# LED_Ring_Dimmer.net
KiCad netlist of a schematic drawn in EAGLE
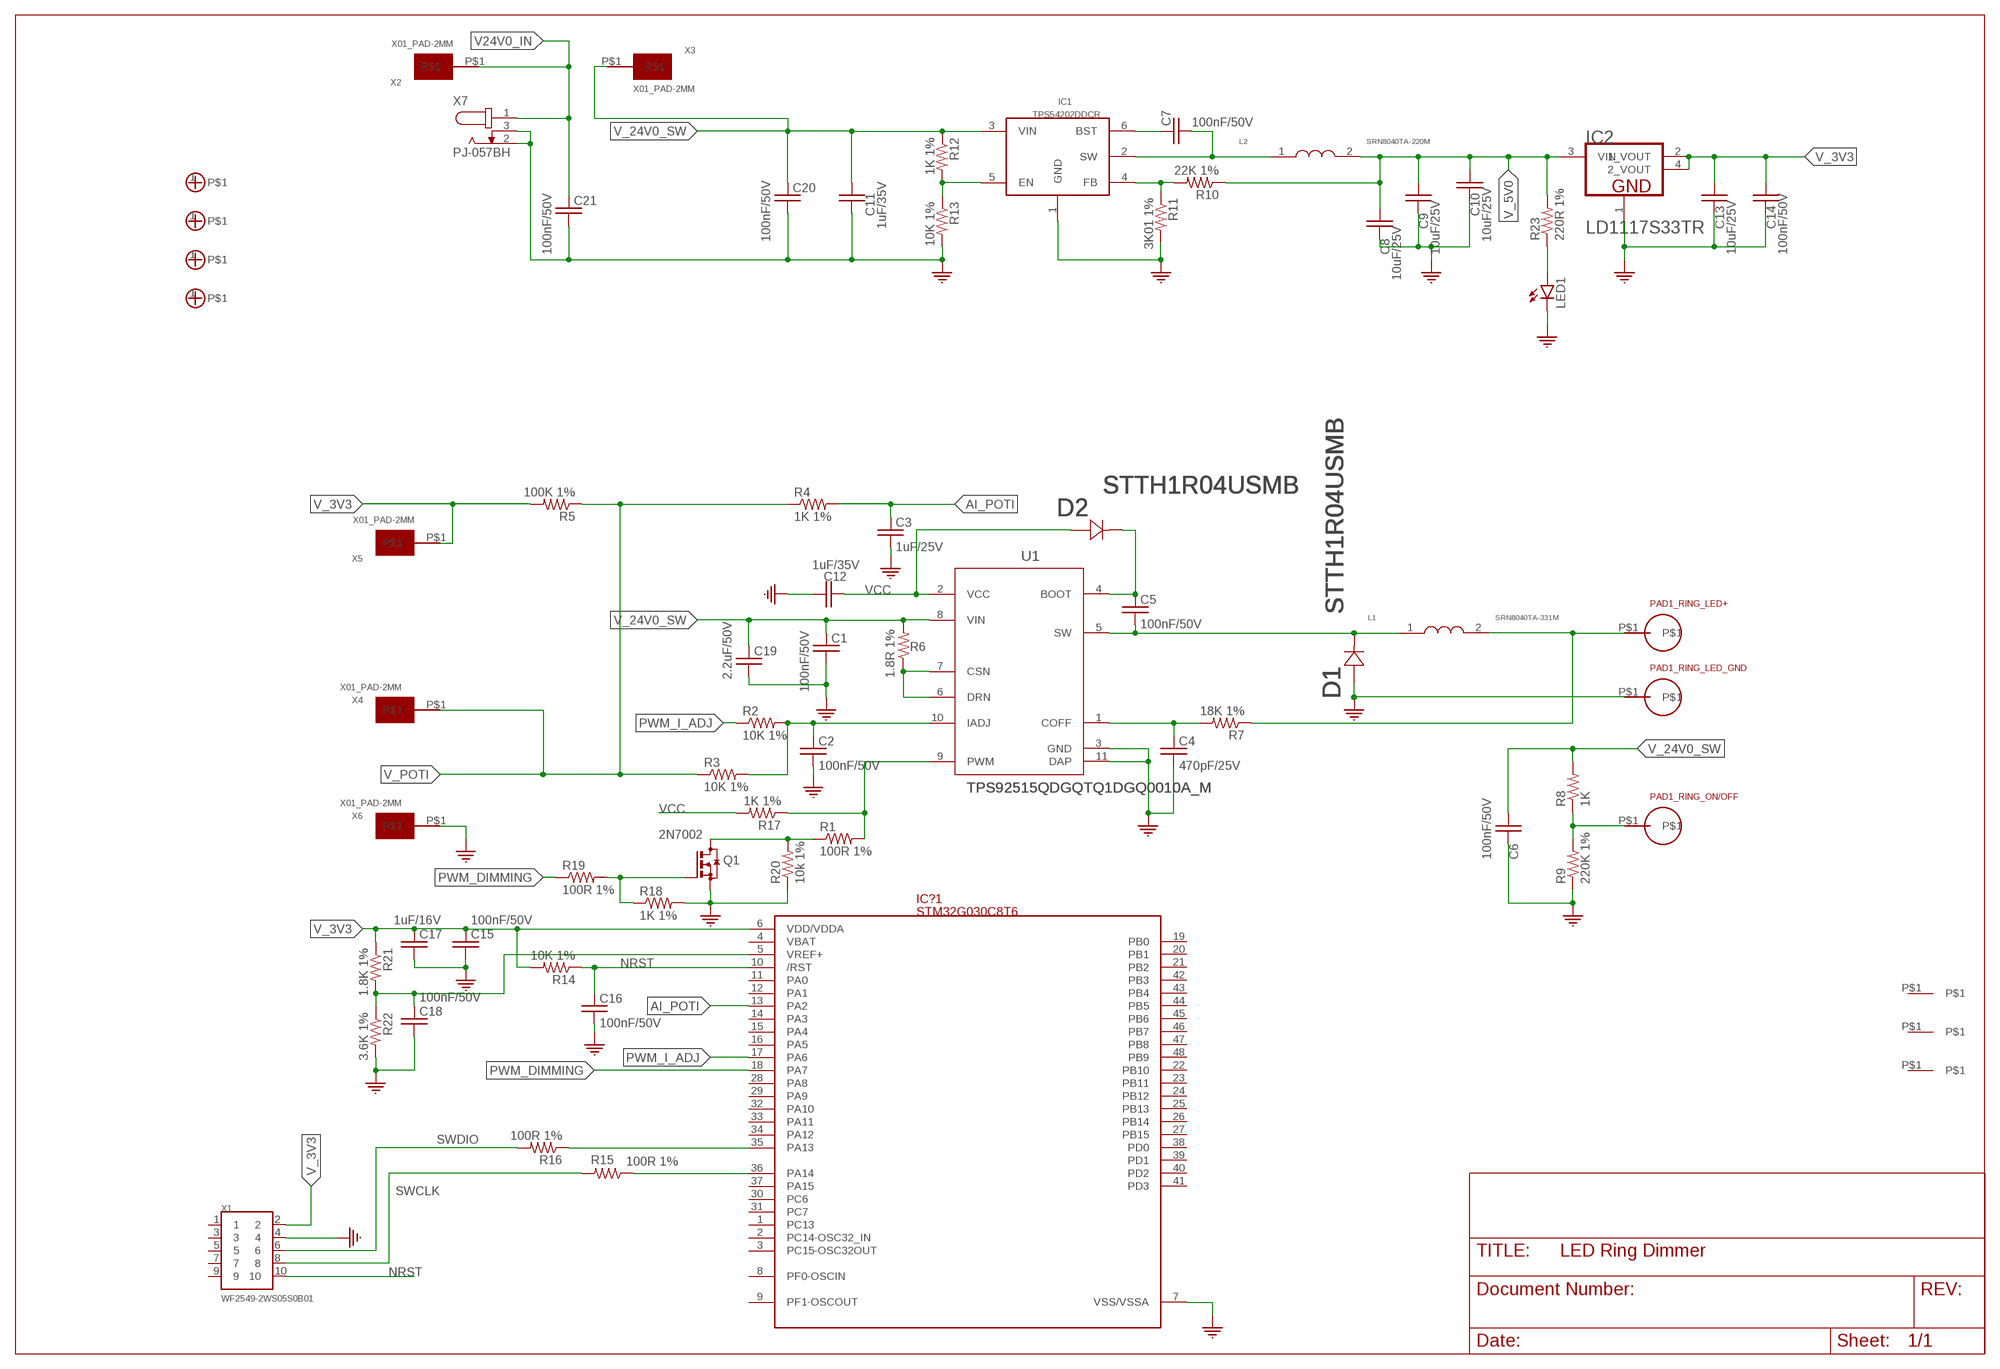
[diagram p0: schematic, sheet 1]

(export (version "E")
  (design (tool "Eeschema 10.0.6"))
  (components
    (comp (ref "C1")
      (value "100nF/50V")
      (footprint "eagle-import:EIA0603")
      (libsource (lib "eagle-import") (part "C_0603EIA0603"))
    )
    (comp (ref "C2")
      (value "100nF/50V")
      (footprint "eagle-import:EIA0603")
      (libsource (lib "eagle-import") (part "C_0603EIA0603"))
    )
    (comp (ref "C3")
      (value "1uF/25V")
      (footprint "eagle-import:EIA0603")
      (libsource (lib "eagle-import") (part "C_0603EIA0603"))
    )
    (comp (ref "C4")
      (value "470pF/25V")
      (footprint "eagle-import:EIA0603")
      (libsource (lib "eagle-import") (part "C_0603EIA0603"))
    )
    (comp (ref "C5")
      (value "100nF/50V")
      (footprint "eagle-import:EIA0603")
      (libsource (lib "eagle-import") (part "C_0603EIA0603"))
    )
    (comp (ref "C6")
      (value "100nF/50V")
      (footprint "eagle-import:EIA0603")
      (libsource (lib "eagle-import") (part "C_0603EIA0603"))
    )
    (comp (ref "C7")
      (value "100nF/50V")
      (footprint "eagle-import:EIA0603")
      (libsource (lib "eagle-import") (part "C_0603EIA0603"))
    )
    (comp (ref "C8")
      (value "10uF/25V")
      (footprint "eagle-import:EIA0603")
      (libsource (lib "eagle-import") (part "C_0603EIA0603"))
    )
    (comp (ref "C9")
      (value "10uF/25V")
      (footprint "eagle-import:EIA0603")
      (libsource (lib "eagle-import") (part "C_0603EIA0603"))
    )
    (comp (ref "C10")
      (value "10uF/25V")
      (footprint "eagle-import:EIA0603")
      (libsource (lib "eagle-import") (part "C_0603EIA0603"))
    )
    (comp (ref "C11")
      (value "1uF/35V")
      (footprint "eagle-import:EIA0603")
      (libsource (lib "eagle-import") (part "C_0603EIA0603"))
    )
    (comp (ref "C12")
      (value "1uF/35V")
      (footprint "eagle-import:EIA0603")
      (libsource (lib "eagle-import") (part "C_0603EIA0603"))
    )
    (comp (ref "C13")
      (value "10uF/25V")
      (footprint "eagle-import:EIA0603")
      (libsource (lib "eagle-import") (part "C_0603EIA0603"))
    )
    (comp (ref "C14")
      (value "100nF/50V")
      (footprint "eagle-import:EIA0603")
      (libsource (lib "eagle-import") (part "C_0603EIA0603"))
    )
    (comp (ref "C15")
      (value "100nF/50V")
      (footprint "eagle-import:EIA0603")
      (libsource (lib "eagle-import") (part "C_0603EIA0603"))
    )
    (comp (ref "C16")
      (value "100nF/50V")
      (footprint "eagle-import:EIA0603")
      (libsource (lib "eagle-import") (part "C_0603EIA0603"))
    )
    (comp (ref "C17")
      (value "1uF/16V")
      (footprint "eagle-import:EIA0603")
      (libsource (lib "eagle-import") (part "C_0603EIA0603"))
    )
    (comp (ref "C18")
      (value "100nF/50V")
      (footprint "eagle-import:EIA0603")
      (libsource (lib "eagle-import") (part "C_0603EIA0603"))
    )
    (comp (ref "C19")
      (value "2.2uF/50V")
      (footprint "eagle-import:EIA0603")
      (libsource (lib "eagle-import") (part "C_0603EIA0603"))
    )
    (comp (ref "C20")
      (value "100nF/50V")
      (footprint "eagle-import:EIA0603")
      (libsource (lib "eagle-import") (part "C_0603EIA0603"))
    )
    (comp (ref "C21")
      (value "100nF/50V")
      (footprint "eagle-import:EIA0603")
      (libsource (lib "eagle-import") (part "C_0603EIA0603"))
    )
    (comp (ref "D1")
      (value "STTH1R04USMB")
      (footprint "eagle-import:SMB")
      (libsource (lib "eagle-import") (part "STTH1R04USMB"))
    )
    (comp (ref "D2")
      (value "STTH1R04USMB")
      (footprint "eagle-import:SMB")
      (libsource (lib "eagle-import") (part "STTH1R04USMB"))
    )
    (comp (ref "FID1")
      (value "FIDUCIAL")
      (footprint "eagle-import:FIDUCIAL")
      (libsource (lib "eagle-import") (part "FIDUCIAL"))
    )
    (comp (ref "FID2")
      (value "FIDUCIAL")
      (footprint "eagle-import:FIDUCIAL")
      (libsource (lib "eagle-import") (part "FIDUCIAL"))
    )
    (comp (ref "FID3")
      (value "FIDUCIAL")
      (footprint "eagle-import:FIDUCIAL")
      (libsource (lib "eagle-import") (part "FIDUCIAL"))
    )
    (comp (ref "IC1")
      (value "TPS54202DDCR")
      (footprint "eagle-import:SOT23-6")
      (fields (field (name "MFR") "Texas Instruments"))
      (libsource (lib "eagle-import") (part "TPS54202DDCR"))
    )
    (comp (ref "IC2")
      (value "LD1117S33TR")
      (footprint "eagle-import:SOT223_LD1117S33TR")
      (fields (field (name "MFR") "STmicro, Diodes, TI,"))
      (libsource (lib "eagle-import") (part "LD1117S33TR"))
    )
    (comp (ref "IC?1")
      (value "STM32G030C8T6")
      (footprint "eagle-import:LQFP48")
      (libsource (lib "eagle-import") (part "STM32G030C8T6"))
    )
    (comp (ref "L1")
      (value "SRN8040TA-331M")
      (footprint "eagle-import:SRN8040TA-220M")
      (fields (field (name "MFR") "Bourns"))
      (libsource (lib "eagle-import") (part "SRN8040TA-331M"))
    )
    (comp (ref "L2")
      (value "SRN8040TA-220M")
      (footprint "eagle-import:SRN8040TA-220M")
      (fields (field (name "MFR") "Bourns"))
      (libsource (lib "eagle-import") (part "SRN8040TA-220M"))
    )
    (comp (ref "LED1")
      (value "LED5MM")
      (footprint "eagle-import:LED5MM")
      (libsource (lib "eagle-import") (part "LED5MM"))
    )
    (comp (ref "M1")
      (value "M_HOLE_3M")
      (footprint "eagle-import:PCB_SCREW_M3_POWER")
      (libsource (lib "eagle-import") (part "M_HOLE_3M"))
    )
    (comp (ref "M2")
      (value "M_HOLE_3M")
      (footprint "eagle-import:PCB_SCREW_M3_POWER")
      (libsource (lib "eagle-import") (part "M_HOLE_3M"))
    )
    (comp (ref "M3")
      (value "M_HOLE_3M")
      (footprint "eagle-import:PCB_SCREW_M3_POWER")
      (libsource (lib "eagle-import") (part "M_HOLE_3M"))
    )
    (comp (ref "M4")
      (value "M_HOLE_3M")
      (footprint "eagle-import:PCB_SCREW_M3_POWER")
      (libsource (lib "eagle-import") (part "M_HOLE_3M"))
    )
    (comp (ref "PAD1_RING_LED+")
      (value "THT_PAD_5MM")
      (footprint "eagle-import:THT_PAD_D5.0")
      (libsource (lib "eagle-import") (part "THT_PAD_5MM"))
    )
    (comp (ref "PAD1_RING_LED_GND")
      (value "THT_PAD_5MM")
      (footprint "eagle-import:THT_PAD_D5.0")
      (libsource (lib "eagle-import") (part "THT_PAD_5MM"))
    )
    (comp (ref "PAD1_RING_ON/OFF")
      (value "THT_PAD_5MM")
      (footprint "eagle-import:THT_PAD_D5.0")
      (libsource (lib "eagle-import") (part "THT_PAD_5MM"))
    )
    (comp (ref "Q1")
      (value "2N7002")
      (footprint "eagle-import:SOT23")
      (fields (field (name "MFR") "Diodes, Guangdong Hotetech,NXP"))
      (libsource (lib "eagle-import") (part "2N7002"))
    )
    (comp (ref "R1")
      (value "100R 1%")
      (footprint "eagle-import:EIA0603")
      (libsource (lib "eagle-import") (part "R_0603"))
    )
    (comp (ref "R2")
      (value "10K 1%")
      (footprint "eagle-import:EIA0603")
      (libsource (lib "eagle-import") (part "R_0603"))
    )
    (comp (ref "R3")
      (value "10K 1%")
      (footprint "eagle-import:EIA0603")
      (libsource (lib "eagle-import") (part "R_0603"))
    )
    (comp (ref "R4")
      (value "1K 1%")
      (footprint "eagle-import:EIA0603")
      (libsource (lib "eagle-import") (part "R_0603"))
    )
    (comp (ref "R5")
      (value "100K 1%")
      (footprint "eagle-import:EIA0603")
      (libsource (lib "eagle-import") (part "R_0603"))
    )
    (comp (ref "R6")
      (value "1.8R 1%")
      (footprint "eagle-import:EIA1206")
      (libsource (lib "eagle-import") (part "R_1206EIA1206"))
    )
    (comp (ref "R7")
      (value "18K 1%")
      (footprint "eagle-import:EIA0603")
      (libsource (lib "eagle-import") (part "R_0603"))
    )
    (comp (ref "R8")
      (value "1K")
      (footprint "eagle-import:EIA0603")
      (libsource (lib "eagle-import") (part "R_0603"))
    )
    (comp (ref "R9")
      (value "220K 1%")
      (footprint "eagle-import:EIA0603")
      (libsource (lib "eagle-import") (part "R_0603"))
    )
    (comp (ref "R10")
      (value "22K 1%")
      (footprint "eagle-import:EIA0603")
      (libsource (lib "eagle-import") (part "R_0603"))
    )
    (comp (ref "R11")
      (value "3K01 1%")
      (footprint "eagle-import:EIA0603")
      (libsource (lib "eagle-import") (part "R_0603"))
    )
    (comp (ref "R12")
      (value "1K 1%")
      (footprint "eagle-import:EIA0603")
      (libsource (lib "eagle-import") (part "R_0603"))
    )
    (comp (ref "R13")
      (value "10K 1%")
      (footprint "eagle-import:EIA0603")
      (libsource (lib "eagle-import") (part "R_0603"))
    )
    (comp (ref "R14")
      (value "10K 1%")
      (footprint "eagle-import:EIA0603")
      (libsource (lib "eagle-import") (part "R_0603"))
    )
    (comp (ref "R15")
      (value "100R 1%")
      (footprint "eagle-import:EIA0603")
      (libsource (lib "eagle-import") (part "R_0603"))
    )
    (comp (ref "R16")
      (value "100R 1%")
      (footprint "eagle-import:EIA0603")
      (libsource (lib "eagle-import") (part "R_0603"))
    )
    (comp (ref "R17")
      (value "1K 1%")
      (footprint "eagle-import:EIA0603")
      (libsource (lib "eagle-import") (part "R_0603"))
    )
    (comp (ref "R18")
      (value "1K 1%")
      (footprint "eagle-import:EIA0603")
      (libsource (lib "eagle-import") (part "R_0603"))
    )
    (comp (ref "R19")
      (value "100R 1%")
      (footprint "eagle-import:EIA0603")
      (libsource (lib "eagle-import") (part "R_0603"))
    )
    (comp (ref "R20")
      (value "10k 1%")
      (footprint "eagle-import:EIA0603")
      (libsource (lib "eagle-import") (part "R_0603"))
    )
    (comp (ref "R21")
      (value "1.8K 1%")
      (footprint "eagle-import:EIA0603")
      (libsource (lib "eagle-import") (part "R_0603"))
    )
    (comp (ref "R22")
      (value "3.6K 1%")
      (footprint "eagle-import:EIA0603")
      (libsource (lib "eagle-import") (part "R_0603"))
    )
    (comp (ref "R23")
      (value "220R 1%")
      (footprint "eagle-import:EIA1206")
      (libsource (lib "eagle-import") (part "R_1206EIA1206"))
    )
    (comp (ref "U1")
      (value "TPS92515QDGQTQ1DGQ0010A_M")
      (footprint "eagle-import:DGQ0010A_M")
      (fields
        (field (name "MFR") "Texas Instruments")
        (field (name "COPYRIGHT") "Copyright (C) 2023 Ultra Librarian. All rights reserved.")
      )
      (libsource (lib "eagle-import") (part "TPS92515QDGQTQ1DGQ0010A_M"))
    )
    (comp (ref "X1")
      (value "WF2549-2WS05S0B01")
      (footprint "eagle-import:X10_100MIL_2XROW_VERT")
      (fields (field (name "MFR") "WCON"))
      (libsource (lib "eagle-import") (part "WF2549-2WS05S0B01"))
    )
    (comp (ref "X2")
      (value "X01_PAD-2MM")
      (footprint "eagle-import:X01_PAD-2MM")
      (libsource (lib "eagle-import") (part "X01_PAD-2MM"))
    )
    (comp (ref "X3")
      (value "X01_PAD-2MM")
      (footprint "eagle-import:X01_PAD-2MM")
      (libsource (lib "eagle-import") (part "X01_PAD-2MM"))
    )
    (comp (ref "X4")
      (value "X01_PAD-2MM")
      (footprint "eagle-import:X01_PAD-2MM")
      (libsource (lib "eagle-import") (part "X01_PAD-2MM"))
    )
    (comp (ref "X5")
      (value "X01_PAD-2MM")
      (footprint "eagle-import:X01_PAD-2MM")
      (libsource (lib "eagle-import") (part "X01_PAD-2MM"))
    )
    (comp (ref "X6")
      (value "X01_PAD-2MM")
      (footprint "eagle-import:X01_PAD-2MM")
      (libsource (lib "eagle-import") (part "X01_PAD-2MM"))
    )
    (comp (ref "X7")
      (value "PJ-057BH")
      (footprint "eagle-import:CUI_PJ-057BH")
      (fields (field (name "MFR") "CUI Devices"))
      (libsource (lib "eagle-import") (part "PJ-057BH"))
    )
  )
  (nets
    (net (code "1") (name "/NRST") (class "Default")
      (node (ref "C16") (pin "1") (pinfunction "1_1") (pintype "passive"))
      (node (ref "IC?1") (pin "10") (pinfunction "/RST_10") (pintype "bidirectional"))
      (node (ref "R14") (pin "1") (pinfunction "1_1") (pintype "passive"))
      (node (ref "X1") (pin "10") (pinfunction "10_10") (pintype "bidirectional"))
    )
    (net (code "2") (name "/SWCLK") (class "Default")
      (node (ref "R15") (pin "2") (pinfunction "2_2") (pintype "passive"))
      (node (ref "X1") (pin "8") (pinfunction "8_8") (pintype "bidirectional"))
    )
    (net (code "3") (name "/SWDIO") (class "Default")
      (node (ref "R16") (pin "2") (pinfunction "2_2") (pintype "passive"))
      (node (ref "X1") (pin "6") (pinfunction "6_6") (pintype "bidirectional"))
    )
    (net (code "4") (name "/VCC") (class "Default")
      (node (ref "C12") (pin "2") (pinfunction "2_2") (pintype "passive"))
      (node (ref "D2") (pin "A") (pinfunction "A_A") (pintype "passive"))
      (node (ref "R17") (pin "2") (pinfunction "2_2") (pintype "passive"))
      (node (ref "U1") (pin "2") (pinfunction "VCC_2") (pintype "power_in"))
    )
    (net (code "5") (name "AI_POTI") (class "Default")
      (node (ref "C3") (pin "1") (pinfunction "1_1") (pintype "passive"))
      (node (ref "IC?1") (pin "13") (pinfunction "PA2_13") (pintype "bidirectional"))
      (node (ref "R4") (pin "2") (pinfunction "2_2") (pintype "passive"))
    )
    (net (code "6") (name "GND") (class "Default")
      (node (ref "C1") (pin "2") (pinfunction "2_2") (pintype "passive"))
      (node (ref "C10") (pin "2") (pinfunction "2_2") (pintype "passive"))
      (node (ref "C11") (pin "2") (pinfunction "2_2") (pintype "passive"))
      (node (ref "C12") (pin "1") (pinfunction "1_1") (pintype "passive"))
      (node (ref "C13") (pin "2") (pinfunction "2_2") (pintype "passive"))
      (node (ref "C14") (pin "2") (pinfunction "2_2") (pintype "passive"))
      (node (ref "C15") (pin "2") (pinfunction "2_2") (pintype "passive"))
      (node (ref "C16") (pin "2") (pinfunction "2_2") (pintype "passive"))
      (node (ref "C17") (pin "2") (pinfunction "2_2") (pintype "passive"))
      (node (ref "C18") (pin "2") (pinfunction "2_2") (pintype "passive"))
      (node (ref "C19") (pin "2") (pinfunction "2_2") (pintype "passive"))
      (node (ref "C2") (pin "2") (pinfunction "2_2") (pintype "passive"))
      (node (ref "C20") (pin "2") (pinfunction "2_2") (pintype "passive"))
      (node (ref "C21") (pin "2") (pinfunction "2_2") (pintype "passive"))
      (node (ref "C3") (pin "2") (pinfunction "2_2") (pintype "passive"))
      (node (ref "C4") (pin "2") (pinfunction "2_2") (pintype "passive"))
      (node (ref "C6") (pin "2") (pinfunction "2_2") (pintype "passive"))
      (node (ref "C8") (pin "2") (pinfunction "2_2") (pintype "passive"))
      (node (ref "C9") (pin "2") (pinfunction "2_2") (pintype "passive"))
      (node (ref "D1") (pin "A") (pinfunction "A_A") (pintype "passive"))
      (node (ref "IC1") (pin "1") (pinfunction "GND_1") (pintype "bidirectional"))
      (node (ref "IC2") (pin "1") (pinfunction "GND_1") (pintype "power_in"))
      (node (ref "IC?1") (pin "7") (pinfunction "VSS/VSSA_7") (pintype "bidirectional"))
      (node (ref "LED1") (pin "K") (pinfunction "C_K") (pintype "passive"))
      (node (ref "PAD1_RING_LED_GND") (pin "P$1") (pinfunction "P$1_P$1") (pintype "bidirectional"))
      (node (ref "Q1") (pin "2") (pinfunction "S_2") (pintype "passive"))
      (node (ref "R11") (pin "2") (pinfunction "2_2") (pintype "passive"))
      (node (ref "R13") (pin "2") (pinfunction "2_2") (pintype "passive"))
      (node (ref "R18") (pin "2") (pinfunction "2_2") (pintype "passive"))
      (node (ref "R20") (pin "1") (pinfunction "1_1") (pintype "passive"))
      (node (ref "R22") (pin "2") (pinfunction "2_2") (pintype "passive"))
      (node (ref "R9") (pin "1") (pinfunction "1_1") (pintype "passive"))
      (node (ref "U1") (pin "11") (pinfunction "DAP_11") (pintype "power_in"))
      (node (ref "U1") (pin "3") (pinfunction "GND_3") (pintype "power_in"))
      (node (ref "X1") (pin "4") (pinfunction "4_4") (pintype "bidirectional"))
      (node (ref "X6") (pin "P$1") (pinfunction "P$1_P$1") (pintype "bidirectional"))
      (node (ref "X7") (pin "2") (pinfunction "2_2") (pintype "passive"))
      (node (ref "X7") (pin "3") (pinfunction "3_3") (pintype "passive"))
    )
    (net (code "7") (name "Net-(D1-C)") (class "Default")
      (node (ref "C5") (pin "2") (pinfunction "2_2") (pintype "passive"))
      (node (ref "D1") (pin "K") (pinfunction "C_K") (pintype "passive"))
      (node (ref "L1") (pin "1") (pinfunction "P$1_1") (pintype "bidirectional"))
      (node (ref "U1") (pin "5") (pinfunction "SW_5") (pintype "power_in"))
    )
    (net (code "8") (name "Net-(D2-C)") (class "Default")
      (node (ref "C5") (pin "1") (pinfunction "1_1") (pintype "passive"))
      (node (ref "D2") (pin "K") (pinfunction "C_K") (pintype "passive"))
      (node (ref "U1") (pin "4") (pinfunction "BOOT_4") (pintype "power_in"))
    )
    (net (code "9") (name "Net-(IC1-BST)") (class "Default")
      (node (ref "C7") (pin "1") (pinfunction "1_1") (pintype "passive"))
      (node (ref "IC1") (pin "6") (pinfunction "BST_6") (pintype "bidirectional"))
    )
    (net (code "10") (name "Net-(IC1-EN)") (class "Default")
      (node (ref "IC1") (pin "5") (pinfunction "EN_5") (pintype "bidirectional"))
      (node (ref "R12") (pin "2") (pinfunction "2_2") (pintype "passive"))
      (node (ref "R13") (pin "1") (pinfunction "1_1") (pintype "passive"))
    )
    (net (code "11") (name "Net-(IC1-FB)") (class "Default")
      (node (ref "IC1") (pin "4") (pinfunction "FB_4") (pintype "bidirectional"))
      (node (ref "R10") (pin "2") (pinfunction "2_2") (pintype "passive"))
      (node (ref "R11") (pin "1") (pinfunction "1_1") (pintype "passive"))
    )
    (net (code "12") (name "Net-(IC1-SW)") (class "Default")
      (node (ref "C7") (pin "2") (pinfunction "2_2") (pintype "passive"))
      (node (ref "IC1") (pin "2") (pinfunction "SW_2") (pintype "bidirectional"))
      (node (ref "L2") (pin "1") (pinfunction "P$1_1") (pintype "bidirectional"))
    )
    (net (code "13") (name "Net-(IC?1-PA13)") (class "Default")
      (node (ref "IC?1") (pin "35") (pinfunction "PA13_35") (pintype "bidirectional"))
      (node (ref "R16") (pin "1") (pinfunction "1_1") (pintype "passive"))
    )
    (net (code "14") (name "Net-(IC?1-PA14)") (class "Default")
      (node (ref "IC?1") (pin "36") (pinfunction "PA14_36") (pintype "bidirectional"))
      (node (ref "R15") (pin "1") (pinfunction "1_1") (pintype "passive"))
    )
    (net (code "15") (name "Net-(IC?1-VREF+)") (class "Default")
      (node (ref "C18") (pin "1") (pinfunction "1_1") (pintype "passive"))
      (node (ref "IC?1") (pin "5") (pinfunction "VREF+_5") (pintype "bidirectional"))
      (node (ref "R21") (pin "2") (pinfunction "2_2") (pintype "passive"))
      (node (ref "R22") (pin "1") (pinfunction "1_1") (pintype "passive"))
    )
    (net (code "16") (name "Net-(L1-P$2)") (class "Default")
      (node (ref "L1") (pin "2") (pinfunction "P$2_2") (pintype "bidirectional"))
      (node (ref "PAD1_RING_LED+") (pin "P$1") (pinfunction "P$1_P$1") (pintype "bidirectional"))
      (node (ref "R7") (pin "1") (pinfunction "1_1") (pintype "passive"))
    )
    (net (code "17") (name "Net-(LED1-PadA)") (class "Default")
      (node (ref "LED1") (pin "A") (pinfunction "A_A") (pintype "passive"))
      (node (ref "R23") (pin "1") (pinfunction "1_1") (pintype "passive"))
    )
    (net (code "18") (name "Net-(PAD1_RING_ON/OFF-PadP$1)") (class "Default")
      (node (ref "PAD1_RING_ON/OFF") (pin "P$1") (pinfunction "P$1_P$1") (pintype "bidirectional"))
      (node (ref "R8") (pin "1") (pinfunction "1_1") (pintype "passive"))
      (node (ref "R9") (pin "2") (pinfunction "2_2") (pintype "passive"))
    )
    (net (code "19") (name "Net-(Q1-D)") (class "Default")
      (node (ref "Q1") (pin "3") (pinfunction "D_3") (pintype "passive"))
      (node (ref "R1") (pin "1") (pinfunction "1_1") (pintype "passive"))
      (node (ref "R20") (pin "2") (pinfunction "2_2") (pintype "passive"))
    )
    (net (code "20") (name "Net-(Q1-G)") (class "Default")
      (node (ref "Q1") (pin "1") (pinfunction "G_1") (pintype "passive"))
      (node (ref "R18") (pin "1") (pinfunction "1_1") (pintype "passive"))
      (node (ref "R19") (pin "2") (pinfunction "2_2") (pintype "passive"))
    )
    (net (code "21") (name "Net-(U1-COFF)") (class "Default")
      (node (ref "C4") (pin "1") (pinfunction "1_1") (pintype "passive"))
      (node (ref "R7") (pin "2") (pinfunction "2_2") (pintype "passive"))
      (node (ref "U1") (pin "1") (pinfunction "COFF_1") (pintype "passive"))
    )
    (net (code "22") (name "Net-(U1-CSN)") (class "Default")
      (node (ref "R6") (pin "1") (pinfunction "1_1") (pintype "passive"))
      (node (ref "U1") (pin "6") (pinfunction "DRN_6") (pintype "passive"))
      (node (ref "U1") (pin "7") (pinfunction "CSN_7") (pintype "input"))
    )
    (net (code "23") (name "Net-(U1-IADJ)") (class "Default")
      (node (ref "C2") (pin "1") (pinfunction "1_1") (pintype "passive"))
      (node (ref "R2") (pin "2") (pinfunction "2_2") (pintype "passive"))
      (node (ref "R3") (pin "2") (pinfunction "2_2") (pintype "passive"))
      (node (ref "U1") (pin "10") (pinfunction "IADJ_10") (pintype "input"))
    )
    (net (code "24") (name "Net-(U1-PWM)") (class "Default")
      (node (ref "R1") (pin "2") (pinfunction "2_2") (pintype "passive"))
      (node (ref "R17") (pin "1") (pinfunction "1_1") (pintype "passive"))
      (node (ref "U1") (pin "9") (pinfunction "PWM_9") (pintype "input"))
    )
    (net (code "25") (name "PWM_DIMMING") (class "Default")
      (node (ref "IC?1") (pin "18") (pinfunction "PA7_18") (pintype "bidirectional"))
      (node (ref "R19") (pin "1") (pinfunction "1_1") (pintype "passive"))
    )
    (net (code "26") (name "PWM_I_ADJ") (class "Default")
      (node (ref "IC?1") (pin "17") (pinfunction "PA6_17") (pintype "bidirectional"))
      (node (ref "R2") (pin "1") (pinfunction "1_1") (pintype "passive"))
    )
    (net (code "27") (name "V24V0_IN") (class "Default")
      (node (ref "C21") (pin "1") (pinfunction "1_1") (pintype "passive"))
      (node (ref "X2") (pin "P$1") (pinfunction "P$1_P$1") (pintype "bidirectional"))
      (node (ref "X7") (pin "1") (pinfunction "1_1") (pintype "passive"))
    )
    (net (code "28") (name "V_3V3") (class "Default")
      (node (ref "C13") (pin "1") (pinfunction "1_1") (pintype "passive"))
      (node (ref "C14") (pin "1") (pinfunction "1_1") (pintype "passive"))
      (node (ref "C15") (pin "1") (pinfunction "1_1") (pintype "passive"))
      (node (ref "C17") (pin "1") (pinfunction "1_1") (pintype "passive"))
      (node (ref "IC2") (pin "2") (pinfunction "1_VOUT_2") (pintype "power_in"))
      (node (ref "IC2") (pin "4") (pinfunction "2_VOUT_4") (pintype "power_in"))
      (node (ref "IC?1") (pin "6") (pinfunction "VDD/VDDA_6") (pintype "bidirectional"))
      (node (ref "R14") (pin "2") (pinfunction "2_2") (pintype "passive"))
      (node (ref "R21") (pin "1") (pinfunction "1_1") (pintype "passive"))
      (node (ref "R5") (pin "2") (pinfunction "2_2") (pintype "passive"))
      (node (ref "X1") (pin "2") (pinfunction "2_2") (pintype "bidirectional"))
      (node (ref "X5") (pin "P$1") (pinfunction "P$1_P$1") (pintype "bidirectional"))
    )
    (net (code "29") (name "V_5V0") (class "Default")
      (node (ref "C10") (pin "1") (pinfunction "1_1") (pintype "passive"))
      (node (ref "C8") (pin "1") (pinfunction "1_1") (pintype "passive"))
      (node (ref "C9") (pin "1") (pinfunction "1_1") (pintype "passive"))
      (node (ref "IC2") (pin "3") (pinfunction "VIN_3") (pintype "power_in"))
      (node (ref "L2") (pin "2") (pinfunction "P$2_2") (pintype "bidirectional"))
      (node (ref "R10") (pin "1") (pinfunction "1_1") (pintype "passive"))
      (node (ref "R23") (pin "2") (pinfunction "2_2") (pintype "passive"))
    )
    (net (code "30") (name "V_24V0_SW") (class "Default")
      (node (ref "C1") (pin "1") (pinfunction "1_1") (pintype "passive"))
      (node (ref "C11") (pin "1") (pinfunction "1_1") (pintype "passive"))
      (node (ref "C19") (pin "1") (pinfunction "1_1") (pintype "passive"))
      (node (ref "C20") (pin "1") (pinfunction "1_1") (pintype "passive"))
      (node (ref "C6") (pin "1") (pinfunction "1_1") (pintype "passive"))
      (node (ref "IC1") (pin "3") (pinfunction "VIN_3") (pintype "bidirectional"))
      (node (ref "R12") (pin "1") (pinfunction "1_1") (pintype "passive"))
      (node (ref "R6") (pin "2") (pinfunction "2_2") (pintype "passive"))
      (node (ref "R8") (pin "2") (pinfunction "2_2") (pintype "passive"))
      (node (ref "U1") (pin "8") (pinfunction "VIN_8") (pintype "power_in"))
      (node (ref "X3") (pin "P$1") (pinfunction "P$1_P$1") (pintype "bidirectional"))
    )
    (net (code "31") (name "V_POTI") (class "Default")
      (node (ref "R3") (pin "1") (pinfunction "1_1") (pintype "passive"))
      (node (ref "R4") (pin "1") (pinfunction "1_1") (pintype "passive"))
      (node (ref "R5") (pin "1") (pinfunction "1_1") (pintype "passive"))
      (node (ref "X4") (pin "P$1") (pinfunction "P$1_P$1") (pintype "bidirectional"))
    )
    (net (code "32") (name "unconnected-(FID1-PadP$1)") (class "Default")
      (node (ref "FID1") (pin "P$1") (pinfunction "P$1_P$1") (pintype "bidirectional"))
    )
    (net (code "33") (name "unconnected-(FID2-PadP$1)") (class "Default")
      (node (ref "FID2") (pin "P$1") (pinfunction "P$1_P$1") (pintype "bidirectional"))
    )
    (net (code "34") (name "unconnected-(FID3-PadP$1)") (class "Default")
      (node (ref "FID3") (pin "P$1") (pinfunction "P$1_P$1") (pintype "bidirectional"))
    )
    (net (code "35") (name "unconnected-(IC?1-PA0-Pad11)") (class "Default")
      (node (ref "IC?1") (pin "11") (pinfunction "PA0_11") (pintype "bidirectional"))
    )
    (net (code "36") (name "unconnected-(IC?1-PA1-Pad12)") (class "Default")
      (node (ref "IC?1") (pin "12") (pinfunction "PA1_12") (pintype "bidirectional"))
    )
    (net (code "37") (name "unconnected-(IC?1-PA3-Pad14)") (class "Default")
      (node (ref "IC?1") (pin "14") (pinfunction "PA3_14") (pintype "bidirectional"))
    )
    (net (code "38") (name "unconnected-(IC?1-PA4-Pad15)") (class "Default")
      (node (ref "IC?1") (pin "15") (pinfunction "PA4_15") (pintype "bidirectional"))
    )
    (net (code "39") (name "unconnected-(IC?1-PA5-Pad16)") (class "Default")
      (node (ref "IC?1") (pin "16") (pinfunction "PA5_16") (pintype "bidirectional"))
    )
    (net (code "40") (name "unconnected-(IC?1-PA8-Pad28)") (class "Default")
      (node (ref "IC?1") (pin "28") (pinfunction "PA8_28") (pintype "bidirectional"))
    )
    (net (code "41") (name "unconnected-(IC?1-PA9-Pad29)") (class "Default")
      (node (ref "IC?1") (pin "29") (pinfunction "PA9_29") (pintype "bidirectional"))
    )
    (net (code "42") (name "unconnected-(IC?1-PA10-Pad32)") (class "Default")
      (node (ref "IC?1") (pin "32") (pinfunction "PA10_32") (pintype "bidirectional"))
    )
    (net (code "43") (name "unconnected-(IC?1-PA11-Pad33)") (class "Default")
      (node (ref "IC?1") (pin "33") (pinfunction "PA11_33") (pintype "bidirectional"))
    )
    (net (code "44") (name "unconnected-(IC?1-PA12-Pad34)") (class "Default")
      (node (ref "IC?1") (pin "34") (pinfunction "PA12_34") (pintype "bidirectional"))
    )
    (net (code "45") (name "unconnected-(IC?1-PA15-Pad37)") (class "Default")
      (node (ref "IC?1") (pin "37") (pinfunction "PA15_37") (pintype "bidirectional"))
    )
    (net (code "46") (name "unconnected-(IC?1-PB0-Pad19)") (class "Default")
      (node (ref "IC?1") (pin "19") (pinfunction "PB0_19") (pintype "bidirectional"))
    )
    (net (code "47") (name "unconnected-(IC?1-PB1-Pad20)") (class "Default")
      (node (ref "IC?1") (pin "20") (pinfunction "PB1_20") (pintype "bidirectional"))
    )
    (net (code "48") (name "unconnected-(IC?1-PB2-Pad21)") (class "Default")
      (node (ref "IC?1") (pin "21") (pinfunction "PB2_21") (pintype "bidirectional"))
    )
    (net (code "49") (name "unconnected-(IC?1-PB3-Pad42)") (class "Default")
      (node (ref "IC?1") (pin "42") (pinfunction "PB3_42") (pintype "bidirectional"))
    )
    (net (code "50") (name "unconnected-(IC?1-PB4-Pad43)") (class "Default")
      (node (ref "IC?1") (pin "43") (pinfunction "PB4_43") (pintype "bidirectional"))
    )
    (net (code "51") (name "unconnected-(IC?1-PB5-Pad44)") (class "Default")
      (node (ref "IC?1") (pin "44") (pinfunction "PB5_44") (pintype "bidirectional"))
    )
    (net (code "52") (name "unconnected-(IC?1-PB6-Pad45)") (class "Default")
      (node (ref "IC?1") (pin "45") (pinfunction "PB6_45") (pintype "bidirectional"))
    )
    (net (code "53") (name "unconnected-(IC?1-PB7-Pad46)") (class "Default")
      (node (ref "IC?1") (pin "46") (pinfunction "PB7_46") (pintype "bidirectional"))
    )
    (net (code "54") (name "unconnected-(IC?1-PB8-Pad47)") (class "Default")
      (node (ref "IC?1") (pin "47") (pinfunction "PB8_47") (pintype "bidirectional"))
    )
    (net (code "55") (name "unconnected-(IC?1-PB9-Pad48)") (class "Default")
      (node (ref "IC?1") (pin "48") (pinfunction "PB9_48") (pintype "bidirectional"))
    )
    (net (code "56") (name "unconnected-(IC?1-PB10-Pad22)") (class "Default")
      (node (ref "IC?1") (pin "22") (pinfunction "PB10_22") (pintype "bidirectional"))
    )
    (net (code "57") (name "unconnected-(IC?1-PB11-Pad23)") (class "Default")
      (node (ref "IC?1") (pin "23") (pinfunction "PB11_23") (pintype "bidirectional"))
    )
    (net (code "58") (name "unconnected-(IC?1-PB12-Pad24)") (class "Default")
      (node (ref "IC?1") (pin "24") (pinfunction "PB12_24") (pintype "bidirectional"))
    )
    (net (code "59") (name "unconnected-(IC?1-PB13-Pad25)") (class "Default")
      (node (ref "IC?1") (pin "25") (pinfunction "PB13_25") (pintype "bidirectional"))
    )
    (net (code "60") (name "unconnected-(IC?1-PB14-Pad26)") (class "Default")
      (node (ref "IC?1") (pin "26") (pinfunction "PB14_26") (pintype "bidirectional"))
    )
    (net (code "61") (name "unconnected-(IC?1-PB15-Pad27)") (class "Default")
      (node (ref "IC?1") (pin "27") (pinfunction "PB15_27") (pintype "bidirectional"))
    )
    (net (code "62") (name "unconnected-(IC?1-PC6-Pad30)") (class "Default")
      (node (ref "IC?1") (pin "30") (pinfunction "PC6_30") (pintype "bidirectional"))
    )
    (net (code "63") (name "unconnected-(IC?1-PC7-Pad31)") (class "Default")
      (node (ref "IC?1") (pin "31") (pinfunction "PC7_31") (pintype "bidirectional"))
    )
    (net (code "64") (name "unconnected-(IC?1-PC13-Pad1)") (class "Default")
      (node (ref "IC?1") (pin "1") (pinfunction "PC13_1") (pintype "bidirectional"))
    )
    (net (code "65") (name "unconnected-(IC?1-PC14-OSC32_IN-Pad2)") (class "Default")
      (node (ref "IC?1") (pin "2") (pinfunction "PC14-OSC32_IN_2") (pintype "bidirectional"))
    )
    (net (code "66") (name "unconnected-(IC?1-PC15-OSC32OUT-Pad3)") (class "Default")
      (node (ref "IC?1") (pin "3") (pinfunction "PC15-OSC32OUT_3") (pintype "bidirectional"))
    )
    (net (code "67") (name "unconnected-(IC?1-PD0-Pad38)") (class "Default")
      (node (ref "IC?1") (pin "38") (pinfunction "PD0_38") (pintype "bidirectional"))
    )
    (net (code "68") (name "unconnected-(IC?1-PD1-Pad39)") (class "Default")
      (node (ref "IC?1") (pin "39") (pinfunction "PD1_39") (pintype "bidirectional"))
    )
    (net (code "69") (name "unconnected-(IC?1-PD2-Pad40)") (class "Default")
      (node (ref "IC?1") (pin "40") (pinfunction "PD2_40") (pintype "bidirectional"))
    )
    (net (code "70") (name "unconnected-(IC?1-PD3-Pad41)") (class "Default")
      (node (ref "IC?1") (pin "41") (pinfunction "PD3_41") (pintype "bidirectional"))
    )
    (net (code "71") (name "unconnected-(IC?1-PF0-OSCIN-Pad8)") (class "Default")
      (node (ref "IC?1") (pin "8") (pinfunction "PF0-OSCIN_8") (pintype "bidirectional"))
    )
    (net (code "72") (name "unconnected-(IC?1-PF1-OSCOUT-Pad9)") (class "Default")
      (node (ref "IC?1") (pin "9") (pinfunction "PF1-OSCOUT_9") (pintype "bidirectional"))
    )
    (net (code "73") (name "unconnected-(IC?1-VBAT-Pad4)") (class "Default")
      (node (ref "IC?1") (pin "4") (pinfunction "VBAT_4") (pintype "bidirectional"))
    )
    (net (code "74") (name "unconnected-(M1-P$1-Pad1)") (class "Default")
      (node (ref "M1") (pin "1") (pinfunction "P$1_1") (pintype "bidirectional"))
    )
    (net (code "75") (name "unconnected-(M2-P$1-Pad1)") (class "Default")
      (node (ref "M2") (pin "1") (pinfunction "P$1_1") (pintype "bidirectional"))
    )
    (net (code "76") (name "unconnected-(M3-P$1-Pad1)") (class "Default")
      (node (ref "M3") (pin "1") (pinfunction "P$1_1") (pintype "bidirectional"))
    )
    (net (code "77") (name "unconnected-(M4-P$1-Pad1)") (class "Default")
      (node (ref "M4") (pin "1") (pinfunction "P$1_1") (pintype "bidirectional"))
    )
    (net (code "78") (name "unconnected-(X1-Pad1)") (class "Default")
      (node (ref "X1") (pin "1") (pinfunction "1_1") (pintype "bidirectional"))
    )
    (net (code "79") (name "unconnected-(X1-Pad3)") (class "Default")
      (node (ref "X1") (pin "3") (pinfunction "3_3") (pintype "bidirectional"))
    )
    (net (code "80") (name "unconnected-(X1-Pad5)") (class "Default")
      (node (ref "X1") (pin "5") (pinfunction "5_5") (pintype "bidirectional"))
    )
    (net (code "81") (name "unconnected-(X1-Pad7)") (class "Default")
      (node (ref "X1") (pin "7") (pinfunction "7_7") (pintype "bidirectional"))
    )
    (net (code "82") (name "unconnected-(X1-Pad9)") (class "Default")
      (node (ref "X1") (pin "9") (pinfunction "9_9") (pintype "bidirectional"))
    )
  )
)
